# CMC_PREAMP.net
KiCad netlist of a schematic drawn in EAGLE
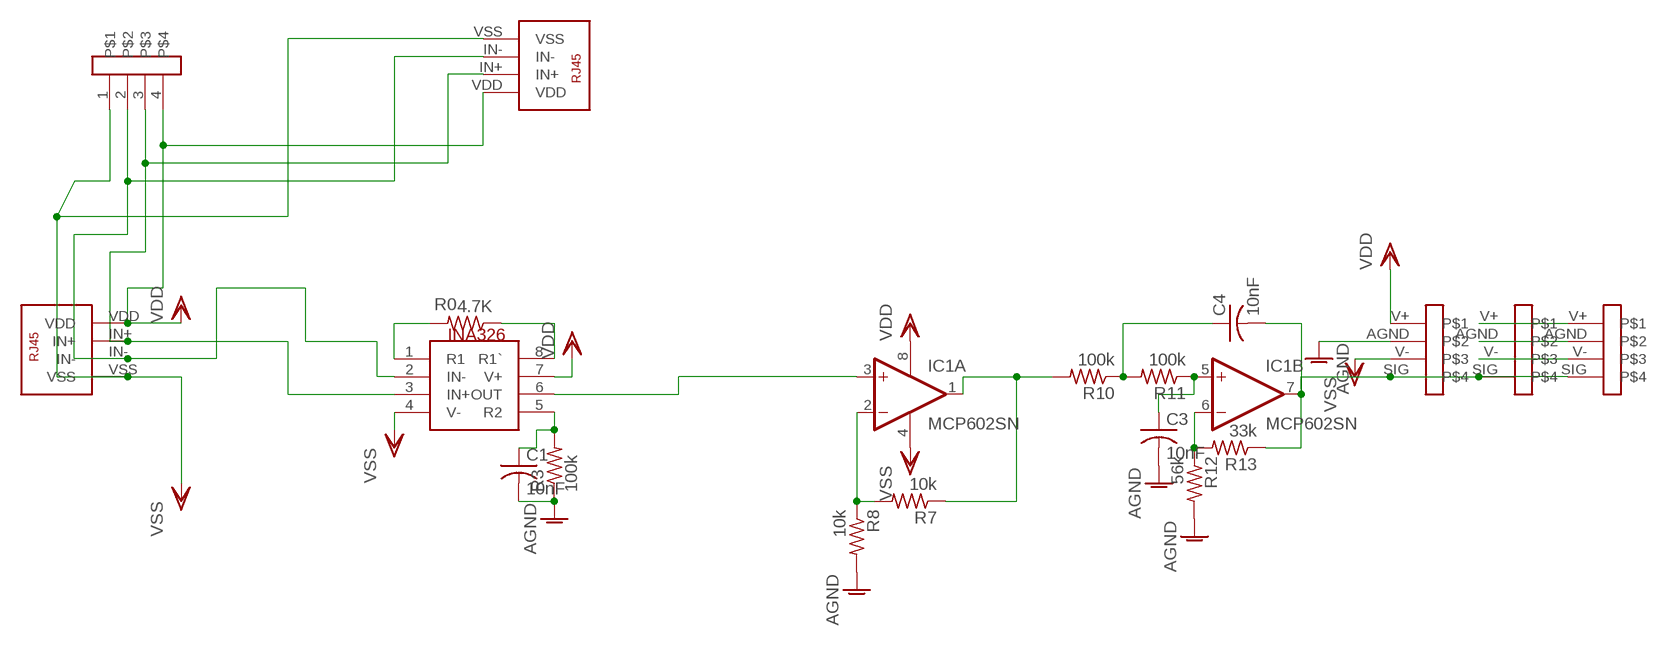
[diagram p0: schematic, sheet 1]

(export (version "E")
  (design (tool "Eeschema 10.0.6"))
  (components
    (comp (ref "C1")
      (value "10nF")
      (footprint "eagle-import:C0603")
      (libsource (lib "eagle-import") (part "C-USC0603"))
    )
    (comp (ref "C3")
      (value "10nF")
      (footprint "eagle-import:C0603")
      (libsource (lib "eagle-import") (part "C-USC0603"))
    )
    (comp (ref "C4")
      (value "10nF")
      (footprint "eagle-import:C0603")
      (libsource (lib "eagle-import") (part "C-USC0603"))
    )
    (comp (ref "IC1")
      (value "MCP602SN")
      (footprint "eagle-import:SO08")
      (libsource (lib "eagle-import") (part "MCP602SN"))
    )
    (comp (ref "R0")
      (value "4.7K")
      (footprint "eagle-import:R0603")
      (libsource (lib "eagle-import") (part "R-US_R0603"))
    )
    (comp (ref "R3")
      (value "100k")
      (footprint "eagle-import:R0603")
      (libsource (lib "eagle-import") (part "R-US_R0603"))
    )
    (comp (ref "R7")
      (value "10k")
      (footprint "eagle-import:R0603")
      (libsource (lib "eagle-import") (part "R-US_R0603"))
    )
    (comp (ref "R8")
      (value "10k")
      (footprint "eagle-import:R0603")
      (libsource (lib "eagle-import") (part "R-US_R0603"))
    )
    (comp (ref "R10")
      (value "100k")
      (footprint "eagle-import:R0603")
      (libsource (lib "eagle-import") (part "R-US_R0603"))
    )
    (comp (ref "R11")
      (value "100k")
      (footprint "eagle-import:R0603")
      (libsource (lib "eagle-import") (part "R-US_R0603"))
    )
    (comp (ref "R12")
      (value "56k")
      (footprint "eagle-import:R0603")
      (libsource (lib "eagle-import") (part "R-US_R0603"))
    )
    (comp (ref "R13")
      (value "33k")
      (footprint "eagle-import:R0603")
      (libsource (lib "eagle-import") (part "R-US_R0603"))
    )
    (comp (ref "U$1")
      (value "CON-4PIN_SILHOLE")
      (footprint "eagle-import:CON-4PIN-SIL")
      (libsource (lib "eagle-import") (part "CON-4PIN_SILHOLE"))
    )
    (comp (ref "U$2")
      (value "CON-4PIN_SIL")
      (footprint "eagle-import:CONN-4PINSIL2")
      (libsource (lib "eagle-import") (part "CON-4PIN_SIL"))
    )
    (comp (ref "U$3")
      (value "CON-4PIN_SIL")
      (footprint "eagle-import:CONN-4PINSIL2")
      (libsource (lib "eagle-import") (part "CON-4PIN_SIL"))
    )
    (comp (ref "U$4")
      (value "RJ45-PRESSUREHOLE")
      (footprint "eagle-import:RJ45")
      (libsource (lib "eagle-import") (part "RJ45-PRESSUREHOLE"))
    )
    (comp (ref "U$6")
      (value "RJ45-PRESSUREHOLE")
      (footprint "eagle-import:RJ45")
      (libsource (lib "eagle-import") (part "RJ45-PRESSUREHOLE"))
    )
    (comp (ref "U$7")
      (value "CON-4PIN_SIL")
      (footprint "eagle-import:CONN-4PINSIL2")
      (libsource (lib "eagle-import") (part "CON-4PIN_SIL"))
    )
    (comp (ref "U$8")
      (value "INA326")
      (footprint "eagle-import:MSOP08")
      (libsource (lib "eagle-import") (part "INA326"))
    )
  )
  (nets
    (net (code "1") (name "AGND") (class "Default")
      (node (ref "C1") (pin "2") (pinfunction "2_2") (pintype "passive"))
      (node (ref "C3") (pin "2") (pinfunction "2_2") (pintype "passive"))
      (node (ref "R12") (pin "2") (pinfunction "2_2") (pintype "passive"))
      (node (ref "R3") (pin "1") (pinfunction "1_1") (pintype "passive"))
      (node (ref "R8") (pin "2") (pinfunction "2_2") (pintype "passive"))
      (node (ref "U$7") (pin "AGND") (pinfunction "P$2_AGND") (pintype "bidirectional"))
    )
    (net (code "2") (name "Net-(C4-Pad1)") (class "Default")
      (node (ref "C4") (pin "1") (pinfunction "1_1") (pintype "passive"))
      (node (ref "R10") (pin "1") (pinfunction "1_1") (pintype "passive"))
      (node (ref "R11") (pin "2") (pinfunction "2_2") (pintype "passive"))
    )
    (net (code "3") (name "Net-(IC1A-+IN)") (class "Default")
      (node (ref "IC1") (pin "3") (pinfunction "+IN_3") (pintype "input"))
      (node (ref "U$8") (pin "6") (pinfunction "OUT_6") (pintype "bidirectional"))
    )
    (net (code "4") (name "Net-(IC1A--IN)") (class "Default")
      (node (ref "IC1") (pin "2") (pinfunction "-IN_2") (pintype "input"))
      (node (ref "R7") (pin "2") (pinfunction "2_2") (pintype "passive"))
      (node (ref "R8") (pin "1") (pinfunction "1_1") (pintype "passive"))
    )
    (net (code "5") (name "Net-(IC1A-OUT)") (class "Default")
      (node (ref "IC1") (pin "1") (pinfunction "OUT_1") (pintype "output"))
      (node (ref "R10") (pin "2") (pinfunction "2_2") (pintype "passive"))
      (node (ref "R7") (pin "1") (pinfunction "1_1") (pintype "passive"))
    )
    (net (code "6") (name "Net-(IC1B-+IN)") (class "Default")
      (node (ref "C3") (pin "1") (pinfunction "1_1") (pintype "passive"))
      (node (ref "IC1") (pin "5") (pinfunction "+IN_5") (pintype "input"))
      (node (ref "R11") (pin "1") (pinfunction "1_1") (pintype "passive"))
    )
    (net (code "7") (name "Net-(IC1B--IN)") (class "Default")
      (node (ref "IC1") (pin "6") (pinfunction "-IN_6") (pintype "input"))
      (node (ref "R12") (pin "1") (pinfunction "1_1") (pintype "passive"))
      (node (ref "R13") (pin "2") (pinfunction "2_2") (pintype "passive"))
    )
    (net (code "8") (name "Net-(IC1B-OUT)") (class "Default")
      (node (ref "C4") (pin "2") (pinfunction "2_2") (pintype "passive"))
      (node (ref "IC1") (pin "7") (pinfunction "OUT_7") (pintype "output"))
      (node (ref "R13") (pin "1") (pinfunction "1_1") (pintype "passive"))
      (node (ref "U$2") (pin "SIG") (pinfunction "P$4_SIG") (pintype "bidirectional"))
      (node (ref "U$3") (pin "SIG") (pinfunction "P$4_SIG") (pintype "bidirectional"))
      (node (ref "U$7") (pin "SIG") (pinfunction "P$4_SIG") (pintype "bidirectional"))
    )
    (net (code "9") (name "Net-(U$1-P$2)") (class "Default")
      (node (ref "U$1") (pin "2") (pinfunction "P$2_2") (pintype "bidirectional"))
      (node (ref "U$4") (pin "IN-") (pinfunction "IN-_IN-") (pintype "bidirectional"))
      (node (ref "U$6") (pin "IN-") (pinfunction "IN-_IN-") (pintype "bidirectional"))
      (node (ref "U$8") (pin "2") (pinfunction "IN-_2") (pintype "bidirectional"))
    )
    (net (code "10") (name "Net-(U$1-P$3)") (class "Default")
      (node (ref "U$1") (pin "3") (pinfunction "P$3_3") (pintype "bidirectional"))
      (node (ref "U$4") (pin "IN+") (pinfunction "IN+_IN+") (pintype "bidirectional"))
      (node (ref "U$6") (pin "IN+") (pinfunction "IN+_IN+") (pintype "bidirectional"))
      (node (ref "U$8") (pin "3") (pinfunction "IN+_3") (pintype "bidirectional"))
    )
    (net (code "11") (name "Net-(U$2-P$1)") (class "Default")
      (node (ref "U$2") (pin "V+") (pinfunction "P$1_V+") (pintype "bidirectional"))
      (node (ref "U$3") (pin "V+") (pinfunction "P$1_V+") (pintype "bidirectional"))
    )
    (net (code "12") (name "Net-(U$2-P$2)") (class "Default")
      (node (ref "U$2") (pin "AGND") (pinfunction "P$2_AGND") (pintype "bidirectional"))
      (node (ref "U$3") (pin "AGND") (pinfunction "P$2_AGND") (pintype "bidirectional"))
    )
    (net (code "13") (name "Net-(U$2-P$3)") (class "Default")
      (node (ref "U$2") (pin "V-") (pinfunction "P$3_V-") (pintype "bidirectional"))
      (node (ref "U$3") (pin "V-") (pinfunction "P$3_V-") (pintype "bidirectional"))
    )
    (net (code "14") (name "Net-(U$8-R1)") (class "Default")
      (node (ref "R0") (pin "2") (pinfunction "2_2") (pintype "passive"))
      (node (ref "U$8") (pin "1") (pinfunction "R1_1") (pintype "bidirectional"))
    )
    (net (code "15") (name "Net-(U$8-R1`)") (class "Default")
      (node (ref "R0") (pin "1") (pinfunction "1_1") (pintype "passive"))
      (node (ref "U$8") (pin "8") (pinfunction "R1`_8") (pintype "bidirectional"))
    )
    (net (code "16") (name "Net-(U$8-R2)") (class "Default")
      (node (ref "C1") (pin "1") (pinfunction "1_1") (pintype "passive"))
      (node (ref "R3") (pin "2") (pinfunction "2_2") (pintype "passive"))
      (node (ref "U$8") (pin "5") (pinfunction "R2_5") (pintype "bidirectional"))
    )
    (net (code "17") (name "VDD") (class "Default")
      (node (ref "IC1") (pin "8") (pinfunction "V+_8") (pintype "power_in"))
      (node (ref "U$1") (pin "4") (pinfunction "P$4_4") (pintype "bidirectional"))
      (node (ref "U$4") (pin "VDD") (pinfunction "VDD_VDD") (pintype "bidirectional"))
      (node (ref "U$6") (pin "VDD") (pinfunction "VDD_VDD") (pintype "bidirectional"))
      (node (ref "U$7") (pin "V+") (pinfunction "P$1_V+") (pintype "bidirectional"))
      (node (ref "U$8") (pin "7") (pinfunction "V+_7") (pintype "bidirectional"))
    )
    (net (code "18") (name "VSS") (class "Default")
      (node (ref "IC1") (pin "4") (pinfunction "V-_4") (pintype "power_in"))
      (node (ref "U$1") (pin "1") (pinfunction "P$1_1") (pintype "bidirectional"))
      (node (ref "U$4") (pin "VSS") (pinfunction "VSS_VSS") (pintype "bidirectional"))
      (node (ref "U$6") (pin "VSS") (pinfunction "VSS_VSS") (pintype "bidirectional"))
      (node (ref "U$7") (pin "V-") (pinfunction "P$3_V-") (pintype "bidirectional"))
      (node (ref "U$8") (pin "4") (pinfunction "V-_4") (pintype "bidirectional"))
    )
  )
)
